# Untitled.net
KiCad netlist of a schematic drawn in EAGLE
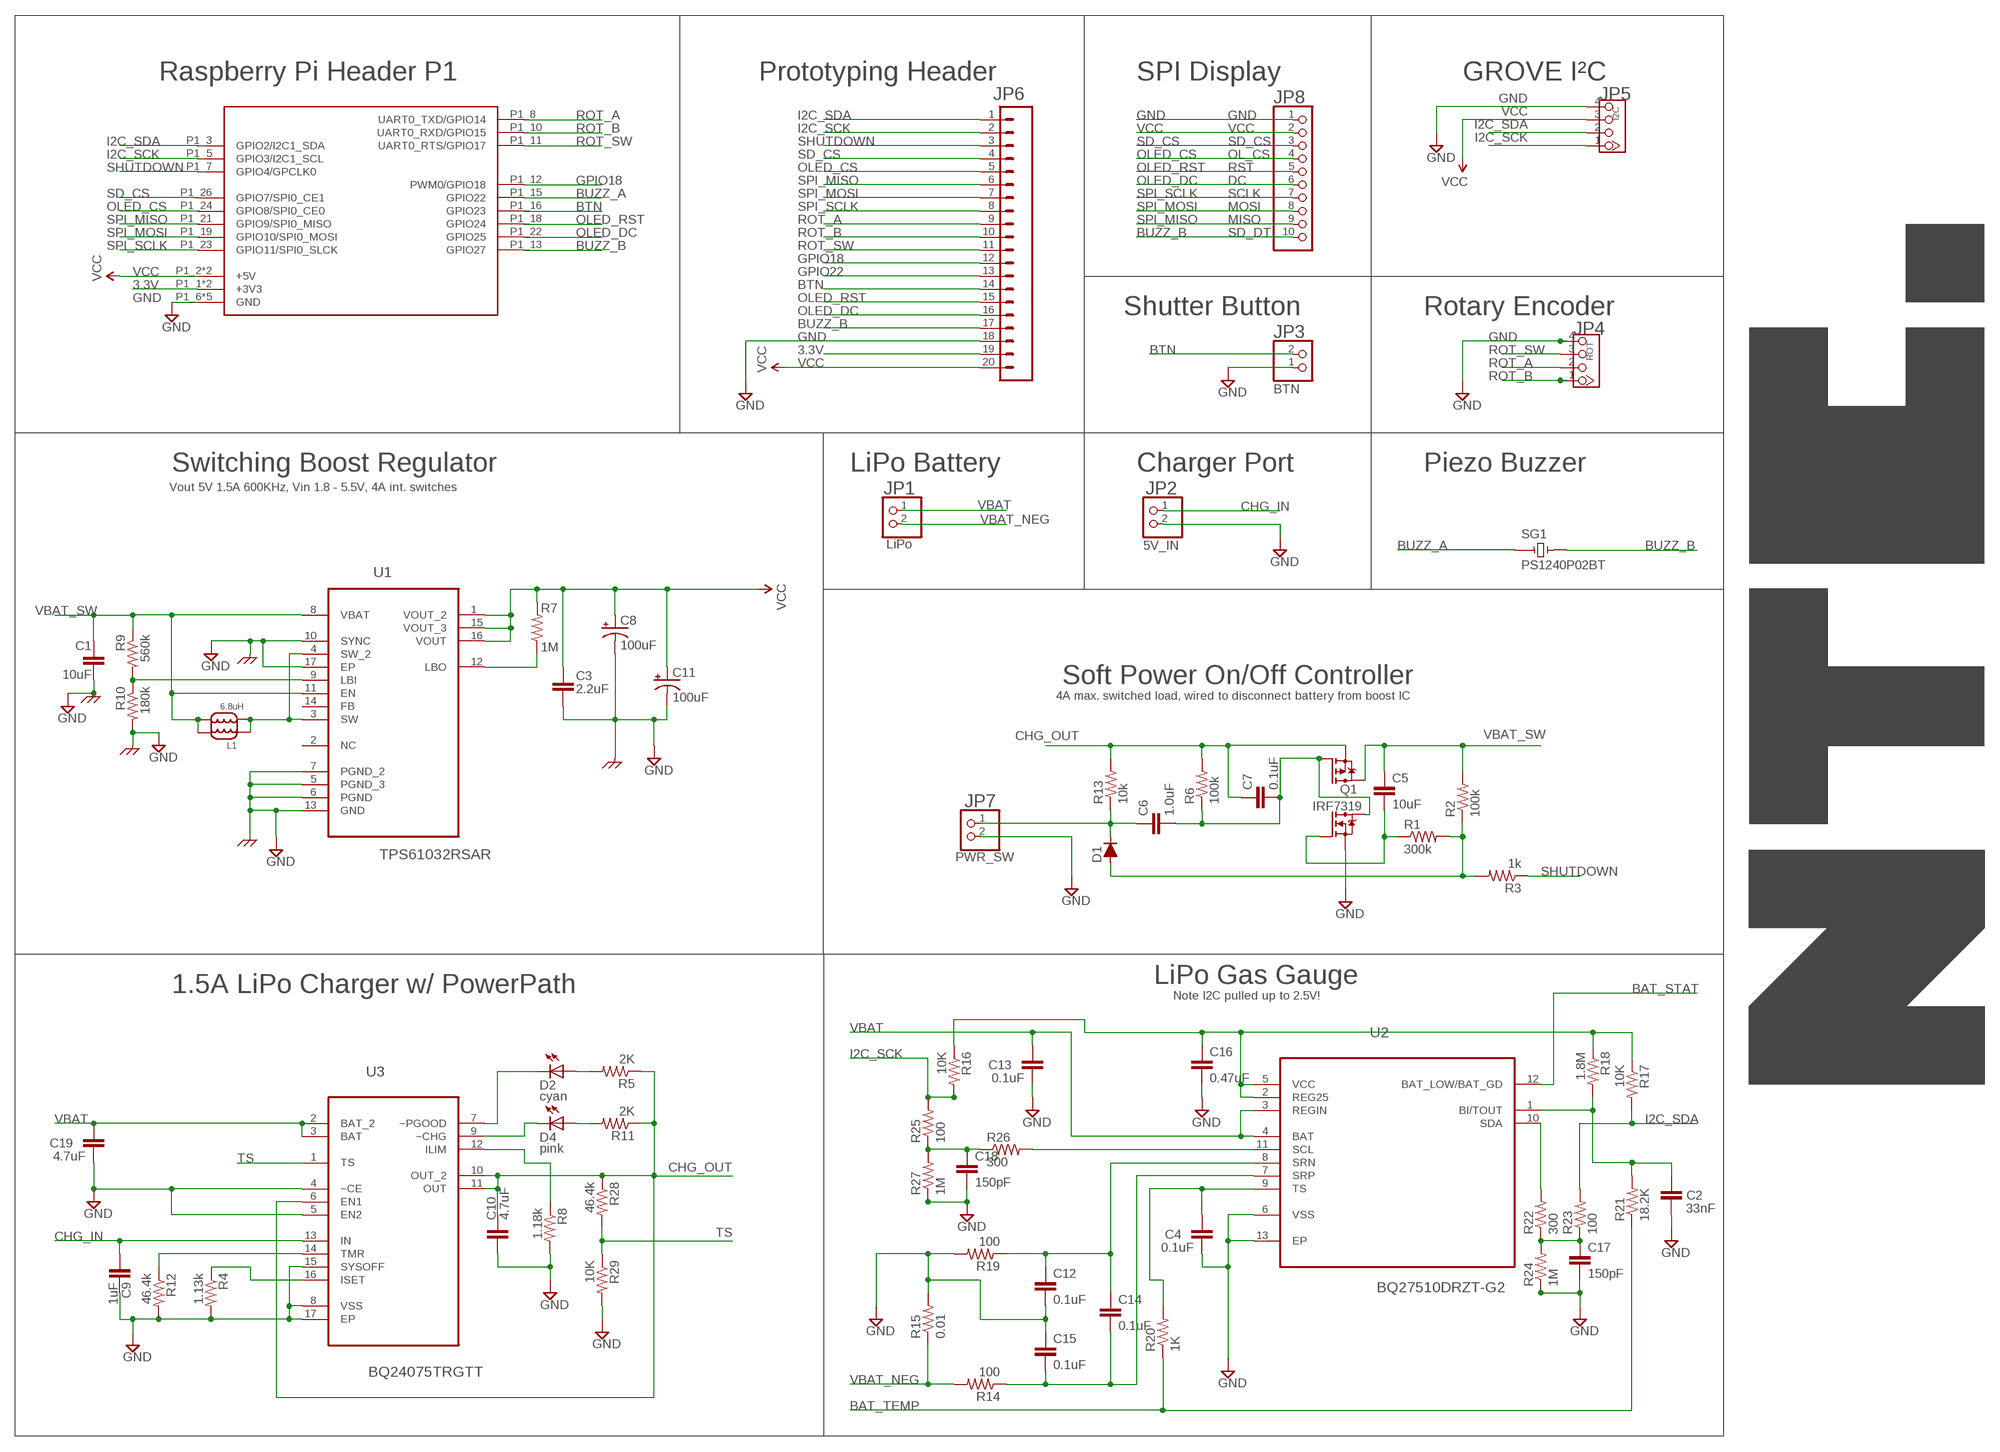
[diagram p0: schematic, sheet 1]

(export (version "E")
  (design (tool "Eeschema 10.0.6"))
  (components
    (comp (ref "C1")
      (value "10uF")
      (footprint "eagle-import:1206")
      (libsource (lib "eagle-import") (part "CAP1206"))
    )
    (comp (ref "C2")
      (value "33nF")
      (footprint "eagle-import:0603-CAP")
      (libsource (lib "eagle-import") (part "CAP0603-CAP"))
    )
    (comp (ref "C3")
      (value "2.2uF")
      (footprint "eagle-import:0603")
      (libsource (lib "eagle-import") (part "CAP0603"))
    )
    (comp (ref "C4")
      (value "0.1uF")
      (footprint "eagle-import:0603-CAP")
      (libsource (lib "eagle-import") (part "CAP0603-CAP"))
    )
    (comp (ref "C5")
      (value "10uF")
      (footprint "eagle-import:0603-CAP")
      (libsource (lib "eagle-import") (part "10UF-6.3V-20%(0603)"))
    )
    (comp (ref "C6")
      (value "1.0uF")
      (footprint "eagle-import:0603-CAP")
      (libsource (lib "eagle-import") (part "1.0UF-16V-10%(0603)"))
    )
    (comp (ref "C7")
      (value "0.1uF")
      (footprint "eagle-import:0603-CAP")
      (libsource (lib "eagle-import") (part "0.1UF-25V-5%(0603)"))
    )
    (comp (ref "C8")
      (value "100uF")
      (footprint "eagle-import:EIA3216")
      (libsource (lib "eagle-import") (part "CAP_POL1206"))
    )
    (comp (ref "C9")
      (value "1uF")
      (footprint "eagle-import:0603-CAP")
      (libsource (lib "eagle-import") (part "CAP0603-CAP"))
    )
    (comp (ref "C10")
      (value "4.7uF")
      (footprint "eagle-import:0603-CAP")
      (libsource (lib "eagle-import") (part "CAP0603-CAP"))
    )
    (comp (ref "C11")
      (value "100uF")
      (footprint "eagle-import:EIA3216")
      (libsource (lib "eagle-import") (part "CAP_POL1206"))
    )
    (comp (ref "C12")
      (value "0.1uF")
      (footprint "eagle-import:0603-CAP")
      (libsource (lib "eagle-import") (part "SparkFun-Capacitors_CAP0603-CAP"))
    )
    (comp (ref "C13")
      (value "0.1uF")
      (footprint "eagle-import:0603-CAP")
      (libsource (lib "eagle-import") (part "CAP0603-CAP"))
    )
    (comp (ref "C14")
      (value "0.1uF")
      (footprint "eagle-import:0603-CAP")
      (libsource (lib "eagle-import") (part "SparkFun-Capacitors_CAP0603-CAP"))
    )
    (comp (ref "C15")
      (value "0.1uF")
      (footprint "eagle-import:0603-CAP")
      (libsource (lib "eagle-import") (part "SparkFun-Capacitors_CAP0603-CAP"))
    )
    (comp (ref "C16")
      (value "0.47uF")
      (footprint "eagle-import:0603-CAP")
      (libsource (lib "eagle-import") (part "SparkFun-Capacitors_CAP0603-CAP"))
    )
    (comp (ref "C17")
      (value "150pF")
      (footprint "eagle-import:0603-CAP")
      (libsource (lib "eagle-import") (part "SparkFun-Capacitors_CAP0603-CAP"))
    )
    (comp (ref "C18")
      (value "150pF")
      (footprint "eagle-import:0603-CAP")
      (libsource (lib "eagle-import") (part "SparkFun-Capacitors_CAP0603-CAP"))
    )
    (comp (ref "C19")
      (value "4.7uF")
      (footprint "eagle-import:0603-CAP")
      (libsource (lib "eagle-import") (part "CAP0603-CAP"))
    )
    (comp (ref "D1")
      (value "D-FILL-SMB")
      (footprint "eagle-import:SMB")
      (libsource (lib "eagle-import") (part "D-FILL-SMB"))
    )
    (comp (ref "D2")
      (value "cyan")
      (footprint "eagle-import:LED-0603")
      (libsource (lib "eagle-import") (part "LED0603"))
    )
    (comp (ref "D4")
      (value "pink")
      (footprint "eagle-import:LED-0603")
      (libsource (lib "eagle-import") (part "LED0603"))
    )
    (comp (ref "JP1")
      (value "LiPo")
      (footprint "eagle-import:JST-PH-2-THM-RA")
      (libsource (lib "eagle-import") (part "JST_2PIN-THM-RA"))
    )
    (comp (ref "JP2")
      (value "5V_IN")
      (footprint "eagle-import:JST-PH-2-THM-RA")
      (libsource (lib "eagle-import") (part "JST_2PIN-THM-RA"))
    )
    (comp (ref "JP3")
      (value "BTN")
      (footprint "eagle-import:JST-PH-2-THM-RA")
      (libsource (lib "eagle-import") (part "JST_2PIN-THM-RA"))
    )
    (comp (ref "JP4")
      (value "ROT")
      (footprint "eagle-import:CONNECTOR_4P-2.0-90D")
      (libsource (lib "eagle-import") (part "CONNECTOR_TWIG-4P-2.090D"))
    )
    (comp (ref "JP5")
      (value "I2C")
      (footprint "eagle-import:CONNECTOR_4P-2.0-90D")
      (libsource (lib "eagle-import") (part "CONNECTOR_TWIG-4P-2.090D"))
    )
    (comp (ref "JP6")
      (value "M20LOCK_LONGPADS")
      (footprint "eagle-import:1X20_LOCK_LONGPADS")
      (libsource (lib "eagle-import") (part "M20LOCK_LONGPADS"))
    )
    (comp (ref "JP7")
      (value "PWR_SW")
      (footprint "eagle-import:JST-PH-2-THM-RA")
      (libsource (lib "eagle-import") (part "JST_2PIN-THM-RA"))
    )
    (comp (ref "JP8")
      (value "PINHD-1X10")
      (footprint "eagle-import:1X10-BIG")
      (libsource (lib "eagle-import") (part "PINHD-1X10"))
    )
    (comp (ref "L1")
      (value "6.8uH")
      (footprint "eagle-import:SUMIDA_CDRH124")
      (libsource (lib "eagle-import") (part "SUMIDA_CDRH124CDRH124NP-6R8MC"))
    )
    (comp (ref "PICAM_SHIELD")
      (value "PICAM_RPI-B-PICAM")
      (footprint "eagle-import:PICAM_RPI-B-PICAM")
      (libsource (lib "eagle-import") (part "PICAM_RPI-B-PICAM"))
    )
    (comp (ref "Q1")
      (value "IRF7319")
      (footprint "eagle-import:SO08-IRF")
      (libsource (lib "eagle-import") (part "IRF7319Q"))
    )
    (comp (ref "R1")
      (value "300k")
      (footprint "eagle-import:0603-RES")
      (libsource (lib "eagle-import") (part "SparkFun-Passives_RESISTOR0603-RES"))
    )
    (comp (ref "R2")
      (value "100k")
      (footprint "eagle-import:0603-RES")
      (libsource (lib "eagle-import") (part "SparkFun-Passives_RESISTOR0603-RES"))
    )
    (comp (ref "R3")
      (value "1k")
      (footprint "eagle-import:0603-RES")
      (libsource (lib "eagle-import") (part "SparkFun-Passives_RESISTOR0603-RES"))
    )
    (comp (ref "R4")
      (value "1.13k")
      (footprint "eagle-import:0603-RES")
      (libsource (lib "eagle-import") (part "RESISTOR0603-RES"))
    )
    (comp (ref "R5")
      (value "2K")
      (footprint "eagle-import:0603-RES")
      (libsource (lib "eagle-import") (part "RESISTOR0603-RES"))
    )
    (comp (ref "R6")
      (value "100k")
      (footprint "eagle-import:0603-RES")
      (libsource (lib "eagle-import") (part "SparkFun-Passives_RESISTOR0603-RES"))
    )
    (comp (ref "R7")
      (value "1M")
      (footprint "eagle-import:0603-RES")
      (libsource (lib "eagle-import") (part "RESISTOR0603-RES"))
    )
    (comp (ref "R8")
      (value "1.18k")
      (footprint "eagle-import:0603-RES")
      (libsource (lib "eagle-import") (part "RESISTOR0603-RES"))
    )
    (comp (ref "R9")
      (value "560k")
      (footprint "eagle-import:0603-RES")
      (libsource (lib "eagle-import") (part "RESISTOR0603-RES"))
    )
    (comp (ref "R10")
      (value "180k")
      (footprint "eagle-import:0603-RES")
      (libsource (lib "eagle-import") (part "RESISTOR0603-RES"))
    )
    (comp (ref "R11")
      (value "2K")
      (footprint "eagle-import:0603-RES")
      (libsource (lib "eagle-import") (part "RESISTOR0603-RES"))
    )
    (comp (ref "R12")
      (value "46.4k")
      (footprint "eagle-import:0603-RES")
      (libsource (lib "eagle-import") (part "RESISTOR0603-RES"))
    )
    (comp (ref "R13")
      (value "10k")
      (footprint "eagle-import:0603-RES")
      (libsource (lib "eagle-import") (part "SparkFun-Passives_RESISTOR0603-RES"))
    )
    (comp (ref "R14")
      (value "100")
      (footprint "eagle-import:0603-RES")
      (libsource (lib "eagle-import") (part "RESISTOR0603-RES"))
    )
    (comp (ref "R15")
      (value "0.01")
      (footprint "eagle-import:SPARKFUN_1206")
      (libsource (lib "eagle-import") (part "SPARKFUN_RESISTOR1206"))
    )
    (comp (ref "R16")
      (value "10K")
      (footprint "eagle-import:0603-RES")
      (libsource (lib "eagle-import") (part "RESISTOR0603-RES"))
    )
    (comp (ref "R17")
      (value "10K")
      (footprint "eagle-import:0603-RES")
      (libsource (lib "eagle-import") (part "RESISTOR0603-RES"))
    )
    (comp (ref "R18")
      (value "1.8M")
      (footprint "eagle-import:0603-RES")
      (libsource (lib "eagle-import") (part "RESISTOR0603-RES"))
    )
    (comp (ref "R19")
      (value "100")
      (footprint "eagle-import:0603-RES")
      (libsource (lib "eagle-import") (part "RESISTOR0603-RES"))
    )
    (comp (ref "R20")
      (value "1K")
      (footprint "eagle-import:SPARKFUN_1206")
      (libsource (lib "eagle-import") (part "SPARKFUN_RESISTOR1206"))
    )
    (comp (ref "R21")
      (value "18.2K")
      (footprint "eagle-import:SPARKFUN_1206")
      (libsource (lib "eagle-import") (part "SPARKFUN_RESISTOR1206"))
    )
    (comp (ref "R22")
      (value "300")
      (footprint "eagle-import:SPARKFUN_1206")
      (libsource (lib "eagle-import") (part "SPARKFUN_RESISTOR1206"))
    )
    (comp (ref "R23")
      (value "100")
      (footprint "eagle-import:SPARKFUN_1206")
      (libsource (lib "eagle-import") (part "SPARKFUN_RESISTOR1206"))
    )
    (comp (ref "R24")
      (value "1M")
      (footprint "eagle-import:SPARKFUN_1206")
      (libsource (lib "eagle-import") (part "SPARKFUN_RESISTOR1206"))
    )
    (comp (ref "R25")
      (value "100")
      (footprint "eagle-import:SPARKFUN_1206")
      (libsource (lib "eagle-import") (part "SPARKFUN_RESISTOR1206"))
    )
    (comp (ref "R26")
      (value "300")
      (footprint "eagle-import:SPARKFUN_1206")
      (libsource (lib "eagle-import") (part "SPARKFUN_RESISTOR1206"))
    )
    (comp (ref "R27")
      (value "1M")
      (footprint "eagle-import:SPARKFUN_1206")
      (libsource (lib "eagle-import") (part "SPARKFUN_RESISTOR1206"))
    )
    (comp (ref "R28")
      (value "46.4k")
      (footprint "eagle-import:0603-RES")
      (libsource (lib "eagle-import") (part "RESISTOR0603-RES"))
    )
    (comp (ref "R29")
      (value "10K")
      (footprint "eagle-import:0603-RES")
      (libsource (lib "eagle-import") (part "RESISTOR0603-RES"))
    )
    (comp (ref "SG1")
      (value "PS1240P02BT")
      (footprint "eagle-import:PS1240")
      (libsource (lib "eagle-import") (part "PS1240P02BT"))
    )
    (comp (ref "U1")
      (value "TPS61032RSAR")
      (footprint "eagle-import:QFN65P400X400X100-17N")
      (libsource (lib "eagle-import") (part "TPS61032RSAR"))
    )
    (comp (ref "U2")
      (value "BQ27510DRZT-G2")
      (footprint "eagle-import:SON40P400X250X100-13N")
      (libsource (lib "eagle-import") (part "BQ27510DRZT-G2"))
    )
    (comp (ref "U3")
      (value "BQ24075TRGTT")
      (footprint "eagle-import:QFN50P300X300X100-17N")
      (libsource (lib "eagle-import") (part "BQ24075TRGTT"))
    )
  )
  (nets
    (net (code "1") (name "3.3V") (class "Default")
      (node (ref "JP6") (pin "19") (pinfunction "19_19") (pintype "passive"))
      (node (ref "PICAM_SHIELD") (pin "P1_1") (pinfunction "+3V3_P1_1") (pintype "power_in"))
      (node (ref "PICAM_SHIELD") (pin "P1_17") (pinfunction "+3V3_P1_17") (pintype "power_in"))
    )
    (net (code "2") (name "BAT_STAT") (class "Default")
      (node (ref "U2") (pin "12") (pinfunction "BAT_LOW/BAT_GD_12") (pintype "output"))
    )
    (net (code "3") (name "BAT_TEMP") (class "Default")
      (node (ref "R20") (pin "1") (pinfunction "1_1") (pintype "passive"))
      (node (ref "R21") (pin "1") (pinfunction "1_1") (pintype "passive"))
    )
    (net (code "4") (name "BTN") (class "Default")
      (node (ref "JP3") (pin "2") (pinfunction "1_2") (pintype "passive"))
      (node (ref "JP6") (pin "14") (pinfunction "14_14") (pintype "passive"))
      (node (ref "PICAM_SHIELD") (pin "P1_16") (pinfunction "GPIO23_P1_16") (pintype "bidirectional"))
    )
    (net (code "5") (name "BUZZ_A") (class "Default")
      (node (ref "PICAM_SHIELD") (pin "P1_15") (pinfunction "GPIO22_P1_15") (pintype "bidirectional"))
      (node (ref "SG1") (pin "P$1") (pinfunction "1_P$1") (pintype "passive"))
    )
    (net (code "6") (name "BUZZ_B") (class "Default")
      (node (ref "JP6") (pin "17") (pinfunction "17_17") (pintype "passive"))
      (node (ref "JP8") (pin "10") (pinfunction "10_10") (pintype "passive"))
      (node (ref "PICAM_SHIELD") (pin "P1_13") (pinfunction "GPIO27_P1_13") (pintype "bidirectional"))
      (node (ref "SG1") (pin "P$2") (pinfunction "2_P$2") (pintype "passive"))
    )
    (net (code "7") (name "CHG_IN") (class "Default")
      (node (ref "C9") (pin "1") (pinfunction "1_1") (pintype "passive"))
      (node (ref "JP2") (pin "1") (pinfunction "2_1") (pintype "passive"))
      (node (ref "U3") (pin "13") (pinfunction "IN_13") (pintype "input"))
    )
    (net (code "8") (name "CHG_OUT") (class "Default")
      (node (ref "C10") (pin "1") (pinfunction "1_1") (pintype "passive"))
      (node (ref "C7") (pin "1") (pinfunction "1_1") (pintype "passive"))
      (node (ref "Q1") (pin "3") (pinfunction "P-S2_3") (pintype "passive"))
      (node (ref "R11") (pin "1") (pinfunction "1_1") (pintype "passive"))
      (node (ref "R13") (pin "2") (pinfunction "2_2") (pintype "passive"))
      (node (ref "R28") (pin "1") (pinfunction "1_1") (pintype "passive"))
      (node (ref "R5") (pin "1") (pinfunction "1_1") (pintype "passive"))
      (node (ref "R6") (pin "2") (pinfunction "2_2") (pintype "passive"))
      (node (ref "U3") (pin "10") (pinfunction "OUT_2_10") (pintype "output"))
      (node (ref "U3") (pin "11") (pinfunction "OUT_11") (pintype "output"))
      (node (ref "U3") (pin "6") (pinfunction "EN1_6") (pintype "input"))
    )
    (net (code "9") (name "GND") (class "Default")
      (node (ref "C1") (pin "2") (pinfunction "2_2") (pintype "passive"))
      (node (ref "C10") (pin "2") (pinfunction "2_2") (pintype "passive"))
      (node (ref "C11") (pin "C") (pinfunction "-_C") (pintype "passive"))
      (node (ref "C12") (pin "2") (pinfunction "2_2") (pintype "passive"))
      (node (ref "C13") (pin "2") (pinfunction "2_2") (pintype "passive"))
      (node (ref "C15") (pin "1") (pinfunction "1_1") (pintype "passive"))
      (node (ref "C16") (pin "2") (pinfunction "2_2") (pintype "passive"))
      (node (ref "C17") (pin "2") (pinfunction "2_2") (pintype "passive"))
      (node (ref "C18") (pin "2") (pinfunction "2_2") (pintype "passive"))
      (node (ref "C19") (pin "2") (pinfunction "2_2") (pintype "passive"))
      (node (ref "C2") (pin "2") (pinfunction "2_2") (pintype "passive"))
      (node (ref "C3") (pin "2") (pinfunction "2_2") (pintype "passive"))
      (node (ref "C4") (pin "2") (pinfunction "2_2") (pintype "passive"))
      (node (ref "C8") (pin "C") (pinfunction "-_C") (pintype "passive"))
      (node (ref "C9") (pin "2") (pinfunction "2_2") (pintype "passive"))
      (node (ref "JP2") (pin "2") (pinfunction "1_2") (pintype "passive"))
      (node (ref "JP3") (pin "1") (pinfunction "2_1") (pintype "passive"))
      (node (ref "JP4") (pin "4") (pinfunction "4_4") (pintype "bidirectional"))
      (node (ref "JP5") (pin "4") (pinfunction "4_4") (pintype "bidirectional"))
      (node (ref "JP6") (pin "18") (pinfunction "18_18") (pintype "passive"))
      (node (ref "JP7") (pin "2") (pinfunction "1_2") (pintype "passive"))
      (node (ref "JP8") (pin "1") (pinfunction "1_1") (pintype "passive"))
      (node (ref "PICAM_SHIELD") (pin "P1_14") (pinfunction "GND_P1_14") (pintype "power_in"))
      (node (ref "PICAM_SHIELD") (pin "P1_20") (pinfunction "GND_P1_20") (pintype "power_in"))
      (node (ref "PICAM_SHIELD") (pin "P1_25") (pinfunction "GND_P1_25") (pintype "power_in"))
      (node (ref "PICAM_SHIELD") (pin "P1_6") (pinfunction "GND_P1_6") (pintype "power_in"))
      (node (ref "PICAM_SHIELD") (pin "P1_9") (pinfunction "GND_P1_9") (pintype "power_in"))
      (node (ref "Q1") (pin "1") (pinfunction "N-S1_1") (pintype "passive"))
      (node (ref "R10") (pin "2") (pinfunction "2_2") (pintype "passive"))
      (node (ref "R12") (pin "2") (pinfunction "2_2") (pintype "passive"))
      (node (ref "R15") (pin "2") (pinfunction "2_2") (pintype "passive"))
      (node (ref "R19") (pin "2") (pinfunction "2_2") (pintype "passive"))
      (node (ref "R24") (pin "1") (pinfunction "1_1") (pintype "passive"))
      (node (ref "R27") (pin "1") (pinfunction "1_1") (pintype "passive"))
      (node (ref "R29") (pin "2") (pinfunction "2_2") (pintype "passive"))
      (node (ref "R4") (pin "2") (pinfunction "2_2") (pintype "passive"))
      (node (ref "R8") (pin "2") (pinfunction "2_2") (pintype "passive"))
      (node (ref "U1") (pin "10") (pinfunction "SYNC_10") (pintype "input"))
      (node (ref "U1") (pin "13") (pinfunction "GND_13") (pintype "passive"))
      (node (ref "U1") (pin "17") (pinfunction "EP_17") (pintype "passive"))
      (node (ref "U1") (pin "5") (pinfunction "PGND_3_5") (pintype "passive"))
      (node (ref "U1") (pin "6") (pinfunction "PGND_6") (pintype "passive"))
      (node (ref "U1") (pin "7") (pinfunction "PGND_2_7") (pintype "passive"))
      (node (ref "U2") (pin "13") (pinfunction "EP_13") (pintype "passive"))
      (node (ref "U2") (pin "6") (pinfunction "VSS_6") (pintype "power_in"))
      (node (ref "U3") (pin "15") (pinfunction "SYSOFF_15") (pintype "input"))
      (node (ref "U3") (pin "17") (pinfunction "EP_17") (pintype "passive"))
      (node (ref "U3") (pin "4") (pinfunction "~{CE}_4") (pintype "input"))
      (node (ref "U3") (pin "5") (pinfunction "EN2_5") (pintype "input"))
      (node (ref "U3") (pin "8") (pinfunction "VSS_8") (pintype "passive"))
    )
    (net (code "10") (name "GPIO18") (class "Default")
      (node (ref "JP6") (pin "12") (pinfunction "12_12") (pintype "passive"))
      (node (ref "PICAM_SHIELD") (pin "P1_12") (pinfunction "PWM0/GPIO18_P1_12") (pintype "bidirectional"))
    )
    (net (code "11") (name "GPIO22") (class "Default")
      (node (ref "JP6") (pin "13") (pinfunction "13_13") (pintype "passive"))
    )
    (net (code "12") (name "I2C_SCK") (class "Default")
      (node (ref "JP5") (pin "1") (pinfunction "1_1") (pintype "bidirectional"))
      (node (ref "JP6") (pin "2") (pinfunction "2_2") (pintype "passive"))
      (node (ref "PICAM_SHIELD") (pin "P1_5") (pinfunction "GPIO3/I2C1_SCL_P1_5") (pintype "bidirectional"))
      (node (ref "R16") (pin "2") (pinfunction "2_2") (pintype "passive"))
      (node (ref "R25") (pin "2") (pinfunction "2_2") (pintype "passive"))
    )
    (net (code "13") (name "I2C_SDA") (class "Default")
      (node (ref "JP5") (pin "2") (pinfunction "2_2") (pintype "bidirectional"))
      (node (ref "JP6") (pin "1") (pinfunction "1_1") (pintype "passive"))
      (node (ref "PICAM_SHIELD") (pin "P1_3") (pinfunction "GPIO2/I2C1_SDA_P1_3") (pintype "bidirectional"))
      (node (ref "R17") (pin "2") (pinfunction "2_2") (pintype "passive"))
      (node (ref "R23") (pin "2") (pinfunction "2_2") (pintype "passive"))
    )
    (net (code "14") (name "Net-(C17-Pad1)") (class "Default")
      (node (ref "C17") (pin "1") (pinfunction "1_1") (pintype "passive"))
      (node (ref "R22") (pin "1") (pinfunction "1_1") (pintype "passive"))
      (node (ref "R23") (pin "1") (pinfunction "1_1") (pintype "passive"))
      (node (ref "R24") (pin "2") (pinfunction "2_2") (pintype "passive"))
    )
    (net (code "15") (name "Net-(C18-Pad1)") (class "Default")
      (node (ref "C18") (pin "1") (pinfunction "1_1") (pintype "passive"))
      (node (ref "R25") (pin "1") (pinfunction "1_1") (pintype "passive"))
      (node (ref "R26") (pin "1") (pinfunction "1_1") (pintype "passive"))
      (node (ref "R27") (pin "2") (pinfunction "2_2") (pintype "passive"))
    )
    (net (code "16") (name "Net-(D1-A)") (class "Default")
      (node (ref "D1") (pin "2") (pinfunction "A_2") (pintype "passive"))
      (node (ref "R1") (pin "2") (pinfunction "2_2") (pintype "passive"))
      (node (ref "R2") (pin "1") (pinfunction "1_1") (pintype "passive"))
      (node (ref "R3") (pin "2") (pinfunction "2_2") (pintype "passive"))
    )
    (net (code "17") (name "Net-(D1-C)") (class "Default")
      (node (ref "C6") (pin "1") (pinfunction "1_1") (pintype "passive"))
      (node (ref "D1") (pin "1") (pinfunction "C_1") (pintype "passive"))
      (node (ref "JP7") (pin "1") (pinfunction "2_1") (pintype "passive"))
      (node (ref "R13") (pin "1") (pinfunction "1_1") (pintype "passive"))
    )
    (net (code "18") (name "Net-(D2-PadA)") (class "Default")
      (node (ref "D2") (pin "A") (pinfunction "A_A") (pintype "passive"))
      (node (ref "R5") (pin "2") (pinfunction "2_2") (pintype "passive"))
    )
    (net (code "19") (name "Net-(D4-PadA)") (class "Default")
      (node (ref "D4") (pin "A") (pinfunction "A_A") (pintype "passive"))
      (node (ref "R11") (pin "2") (pinfunction "2_2") (pintype "passive"))
    )
    (net (code "20") (name "Net-(Q1-N-G1)") (class "Default")
      (node (ref "C5") (pin "2") (pinfunction "2_2") (pintype "passive"))
      (node (ref "Q1") (pin "2") (pinfunction "N-G1_2") (pintype "passive"))
      (node (ref "R1") (pin "1") (pinfunction "1_1") (pintype "passive"))
    )
    (net (code "21") (name "Net-(Q1-P-G2)") (class "Default")
      (node (ref "C6") (pin "2") (pinfunction "2_2") (pintype "passive"))
      (node (ref "C7") (pin "2") (pinfunction "2_2") (pintype "passive"))
      (node (ref "Q1") (pin "4") (pinfunction "P-G2_4") (pintype "passive"))
      (node (ref "Q1") (pin "7") (pinfunction "N-D1_7") (pintype "passive"))
      (node (ref "Q1") (pin "8") (pinfunction "N-D1_8") (pintype "passive"))
      (node (ref "R6") (pin "1") (pinfunction "1_1") (pintype "passive"))
    )
    (net (code "22") (name "Net-(U1-LBI)") (class "Default")
      (node (ref "R10") (pin "1") (pinfunction "1_1") (pintype "passive"))
      (node (ref "R9") (pin "2") (pinfunction "2_2") (pintype "passive"))
      (node (ref "U1") (pin "9") (pinfunction "LBI_9") (pintype "input"))
    )
    (net (code "23") (name "Net-(U1-LBO)") (class "Default")
      (node (ref "R7") (pin "1") (pinfunction "1_1") (pintype "passive"))
      (node (ref "U1") (pin "12") (pinfunction "LBO_12") (pintype "output"))
    )
    (net (code "24") (name "Net-(U1-SW)") (class "Default")
      (node (ref "L1") (pin "P$3") (pinfunction "2_P$3") (pintype "passive"))
      (node (ref "L1") (pin "P$4") (pinfunction "2_P$4") (pintype "passive"))
      (node (ref "U1") (pin "3") (pinfunction "SW_3") (pintype "input"))
      (node (ref "U1") (pin "4") (pinfunction "SW_2_4") (pintype "input"))
    )
    (net (code "25") (name "Net-(U2-BI{slash}TOUT)") (class "Default")
      (node (ref "C2") (pin "1") (pinfunction "1_1") (pintype "passive"))
      (node (ref "R18") (pin "2") (pinfunction "2_2") (pintype "passive"))
      (node (ref "R21") (pin "2") (pinfunction "2_2") (pintype "passive"))
      (node (ref "U2") (pin "1") (pinfunction "BI/TOUT_1") (pintype "bidirectional"))
    )
    (net (code "26") (name "Net-(U2-REG25)") (class "Default")
      (node (ref "C16") (pin "1") (pinfunction "1_1") (pintype "passive"))
      (node (ref "R16") (pin "1") (pinfunction "1_1") (pintype "passive"))
      (node (ref "R17") (pin "1") (pinfunction "1_1") (pintype "passive"))
      (node (ref "R18") (pin "1") (pinfunction "1_1") (pintype "passive"))
      (node (ref "U2") (pin "2") (pinfunction "REG25_2") (pintype "power_in"))
      (node (ref "U2") (pin "5") (pinfunction "VCC_5") (pintype "power_in"))
    )
    (net (code "27") (name "Net-(U2-SCL)") (class "Default")
      (node (ref "R26") (pin "2") (pinfunction "2_2") (pintype "passive"))
      (node (ref "U2") (pin "11") (pinfunction "SCL_11") (pintype "input"))
    )
    (net (code "28") (name "Net-(U2-SDA)") (class "Default")
      (node (ref "R22") (pin "2") (pinfunction "2_2") (pintype "passive"))
      (node (ref "U2") (pin "10") (pinfunction "SDA_10") (pintype "bidirectional"))
    )
    (net (code "29") (name "Net-(U2-SRN)") (class "Default")
      (node (ref "C12") (pin "1") (pinfunction "1_1") (pintype "passive"))
      (node (ref "C14") (pin "1") (pinfunction "1_1") (pintype "passive"))
      (node (ref "R19") (pin "1") (pinfunction "1_1") (pintype "passive"))
      (node (ref "U2") (pin "8") (pinfunction "SRN_8") (pintype "input"))
    )
    (net (code "30") (name "Net-(U2-SRP)") (class "Default")
      (node (ref "C14") (pin "2") (pinfunction "2_2") (pintype "passive"))
      (node (ref "C15") (pin "2") (pinfunction "2_2") (pintype "passive"))
      (node (ref "R14") (pin "1") (pinfunction "1_1") (pintype "passive"))
      (node (ref "U2") (pin "7") (pinfunction "SRP_7") (pintype "input"))
    )
    (net (code "31") (name "Net-(U2-TS)") (class "Default")
      (node (ref "C4") (pin "1") (pinfunction "1_1") (pintype "passive"))
      (node (ref "R20") (pin "2") (pinfunction "2_2") (pintype "passive"))
      (node (ref "U2") (pin "9") (pinfunction "TS_9") (pintype "input"))
    )
    (net (code "32") (name "Net-(U3-ILIM)") (class "Default")
      (node (ref "R8") (pin "1") (pinfunction "1_1") (pintype "passive"))
      (node (ref "U3") (pin "12") (pinfunction "ILIM_12") (pintype "output"))
    )
    (net (code "33") (name "Net-(U3-ISET)") (class "Default")
      (node (ref "R4") (pin "1") (pinfunction "1_1") (pintype "passive"))
      (node (ref "U3") (pin "16") (pinfunction "ISET_16") (pintype "bidirectional"))
    )
    (net (code "34") (name "Net-(U3-TMR)") (class "Default")
      (node (ref "R12") (pin "1") (pinfunction "1_1") (pintype "passive"))
      (node (ref "U3") (pin "14") (pinfunction "TMR_14") (pintype "input"))
    )
    (net (code "35") (name "Net-(U3-~{CHG})") (class "Default")
      (node (ref "D4") (pin "C") (pinfunction "C_C") (pintype "passive"))
      (node (ref "U3") (pin "9") (pinfunction "~{CHG}_9") (pintype "output"))
    )
    (net (code "36") (name "Net-(U3-~{PGOOD})") (class "Default")
      (node (ref "D2") (pin "C") (pinfunction "C_C") (pintype "passive"))
      (node (ref "U3") (pin "7") (pinfunction "~{PGOOD}_7") (pintype "output"))
    )
    (net (code "37") (name "OLED_CS") (class "Default")
      (node (ref "JP6") (pin "5") (pinfunction "5_5") (pintype "passive"))
      (node (ref "JP8") (pin "4") (pinfunction "4_4") (pintype "passive"))
      (node (ref "PICAM_SHIELD") (pin "P1_24") (pinfunction "GPIO8/SPI0_CE0_P1_24") (pintype "bidirectional"))
    )
    (net (code "38") (name "OLED_DC") (class "Default")
      (node (ref "JP6") (pin "16") (pinfunction "16_16") (pintype "passive"))
      (node (ref "JP8") (pin "6") (pinfunction "6_6") (pintype "passive"))
      (node (ref "PICAM_SHIELD") (pin "P1_22") (pinfunction "GPIO25_P1_22") (pintype "bidirectional"))
    )
    (net (code "39") (name "OLED_RST") (class "Default")
      (node (ref "JP6") (pin "15") (pinfunction "15_15") (pintype "passive"))
      (node (ref "JP8") (pin "5") (pinfunction "5_5") (pintype "passive"))
      (node (ref "PICAM_SHIELD") (pin "P1_18") (pinfunction "GPIO24_P1_18") (pintype "bidirectional"))
    )
    (net (code "40") (name "ROT_A") (class "Default")
      (node (ref "JP4") (pin "2") (pinfunction "2_2") (pintype "bidirectional"))
      (node (ref "JP6") (pin "9") (pinfunction "9_9") (pintype "passive"))
      (node (ref "PICAM_SHIELD") (pin "P1_8") (pinfunction "UART0_TXD/GPIO14_P1_8") (pintype "bidirectional"))
    )
    (net (code "41") (name "ROT_B") (class "Default")
      (node (ref "JP4") (pin "1") (pinfunction "1_1") (pintype "bidirectional"))
      (node (ref "JP6") (pin "10") (pinfunction "10_10") (pintype "passive"))
      (node (ref "PICAM_SHIELD") (pin "P1_10") (pinfunction "UART0_RXD/GPIO15_P1_10") (pintype "bidirectional"))
    )
    (net (code "42") (name "ROT_SW") (class "Default")
      (node (ref "JP4") (pin "3") (pinfunction "3_3") (pintype "bidirectional"))
      (node (ref "JP6") (pin "11") (pinfunction "11_11") (pintype "passive"))
      (node (ref "PICAM_SHIELD") (pin "P1_11") (pinfunction "UART0_RTS/GPIO17_P1_11") (pintype "bidirectional"))
    )
    (net (code "43") (name "SD_CS") (class "Default")
      (node (ref "JP6") (pin "4") (pinfunction "4_4") (pintype "passive"))
      (node (ref "JP8") (pin "3") (pinfunction "3_3") (pintype "passive"))
      (node (ref "PICAM_SHIELD") (pin "P1_26") (pinfunction "GPIO7/SPI0_CE1_P1_26") (pintype "bidirectional"))
    )
    (net (code "44") (name "SHUTDOWN") (class "Default")
      (node (ref "JP6") (pin "3") (pinfunction "3_3") (pintype "passive"))
      (node (ref "PICAM_SHIELD") (pin "P1_7") (pinfunction "GPIO4/GPCLK0_P1_7") (pintype "bidirectional"))
      (node (ref "R3") (pin "1") (pinfunction "1_1") (pintype "passive"))
    )
    (net (code "45") (name "SPI_MISO") (class "Default")
      (node (ref "JP6") (pin "6") (pinfunction "6_6") (pintype "passive"))
      (node (ref "JP8") (pin "9") (pinfunction "9_9") (pintype "passive"))
      (node (ref "PICAM_SHIELD") (pin "P1_21") (pinfunction "GPIO9/SPI0_MISO_P1_21") (pintype "bidirectional"))
    )
    (net (code "46") (name "SPI_MOSI") (class "Default")
      (node (ref "JP6") (pin "7") (pinfunction "7_7") (pintype "passive"))
      (node (ref "JP8") (pin "8") (pinfunction "8_8") (pintype "passive"))
      (node (ref "PICAM_SHIELD") (pin "P1_19") (pinfunction "GPIO10/SPI0_MOSI_P1_19") (pintype "bidirectional"))
    )
    (net (code "47") (name "SPI_SCLK") (class "Default")
      (node (ref "JP6") (pin "8") (pinfunction "8_8") (pintype "passive"))
      (node (ref "JP8") (pin "7") (pinfunction "7_7") (pintype "passive"))
      (node (ref "PICAM_SHIELD") (pin "P1_23") (pinfunction "GPIO11/SPI0_SLCK_P1_23") (pintype "bidirectional"))
    )
    (net (code "48") (name "TS") (class "Default")
      (node (ref "R28") (pin "2") (pinfunction "2_2") (pintype "passive"))
      (node (ref "R29") (pin "1") (pinfunction "1_1") (pintype "passive"))
      (node (ref "U3") (pin "1") (pinfunction "TS_1") (pintype "bidirectional"))
    )
    (net (code "49") (name "VBAT") (class "Default")
      (node (ref "C13") (pin "1") (pinfunction "1_1") (pintype "passive"))
      (node (ref "C19") (pin "1") (pinfunction "1_1") (pintype "passive"))
      (node (ref "JP1") (pin "1") (pinfunction "2_1") (pintype "passive"))
      (node (ref "U2") (pin "3") (pinfunction "REGIN_3") (pintype "power_in"))
      (node (ref "U2") (pin "4") (pinfunction "BAT_4") (pintype "input"))
      (node (ref "U3") (pin "2") (pinfunction "BAT_2_2") (pintype "bidirectional"))
      (node (ref "U3") (pin "3") (pinfunction "BAT_3") (pintype "bidirectional"))
    )
    (net (code "50") (name "VBAT_NEG") (class "Default")
      (node (ref "JP1") (pin "2") (pinfunction "1_2") (pintype "passive"))
      (node (ref "R14") (pin "2") (pinfunction "2_2") (pintype "passive"))
      (node (ref "R15") (pin "1") (pinfunction "1_1") (pintype "passive"))
    )
    (net (code "51") (name "VBAT_SW") (class "Default")
      (node (ref "C1") (pin "1") (pinfunction "1_1") (pintype "passive"))
      (node (ref "C5") (pin "1") (pinfunction "1_1") (pintype "passive"))
      (node (ref "L1") (pin "P$1") (pinfunction "1_P$1") (pintype "passive"))
      (node (ref "L1") (pin "P$2") (pinfunction "1_P$2") (pintype "passive"))
      (node (ref "Q1") (pin "5") (pinfunction "P-D2_5") (pintype "passive"))
      (node (ref "Q1") (pin "6") (pinfunction "P-D2_6") (pintype "passive"))
      (node (ref "R2") (pin "2") (pinfunction "2_2") (pintype "passive"))
      (node (ref "R9") (pin "1") (pinfunction "1_1") (pintype "passive"))
      (node (ref "U1") (pin "11") (pinfunction "EN_11") (pintype "input"))
      (node (ref "U1") (pin "8") (pinfunction "VBAT_8") (pintype "input"))
    )
    (net (code "52") (name "VCC") (class "Default")
      (node (ref "C11") (pin "A") (pinfunction "+_A") (pintype "passive"))
      (node (ref "C3") (pin "1") (pinfunction "1_1") (pintype "passive"))
      (node (ref "C8") (pin "A") (pinfunction "+_A") (pintype "passive"))
      (node (ref "JP5") (pin "3") (pinfunction "3_3") (pintype "bidirectional"))
      (node (ref "JP6") (pin "20") (pinfunction "20_20") (pintype "passive"))
      (node (ref "JP8") (pin "2") (pinfunction "2_2") (pintype "passive"))
      (node (ref "PICAM_SHIELD") (pin "P1_2") (pinfunction "+5V_P1_2") (pintype "power_in"))
      (node (ref "PICAM_SHIELD") (pin "P1_4") (pinfunction "+5V_P1_4") (pintype "power_in"))
      (node (ref "R7") (pin "2") (pinfunction "2_2") (pintype "passive"))
      (node (ref "U1") (pin "1") (pinfunction "VOUT_2_1") (pintype "output"))
      (node (ref "U1") (pin "15") (pinfunction "VOUT_3_15") (pintype "output"))
      (node (ref "U1") (pin "16") (pinfunction "VOUT_16") (pintype "output"))
    )
    (net (code "53") (name "unconnected-(U1-FB-Pad14)") (class "Default")
      (node (ref "U1") (pin "14") (pinfunction "FB_14") (pintype "input"))
    )
    (net (code "54") (name "unconnected-(U1-NC-Pad2)") (class "Default")
      (node (ref "U1") (pin "2") (pinfunction "NC_2") (pintype "no_connect"))
    )
  )
)
